# AdaptadorAcceso.net
KiCad netlist of a schematic drawn in EAGLE
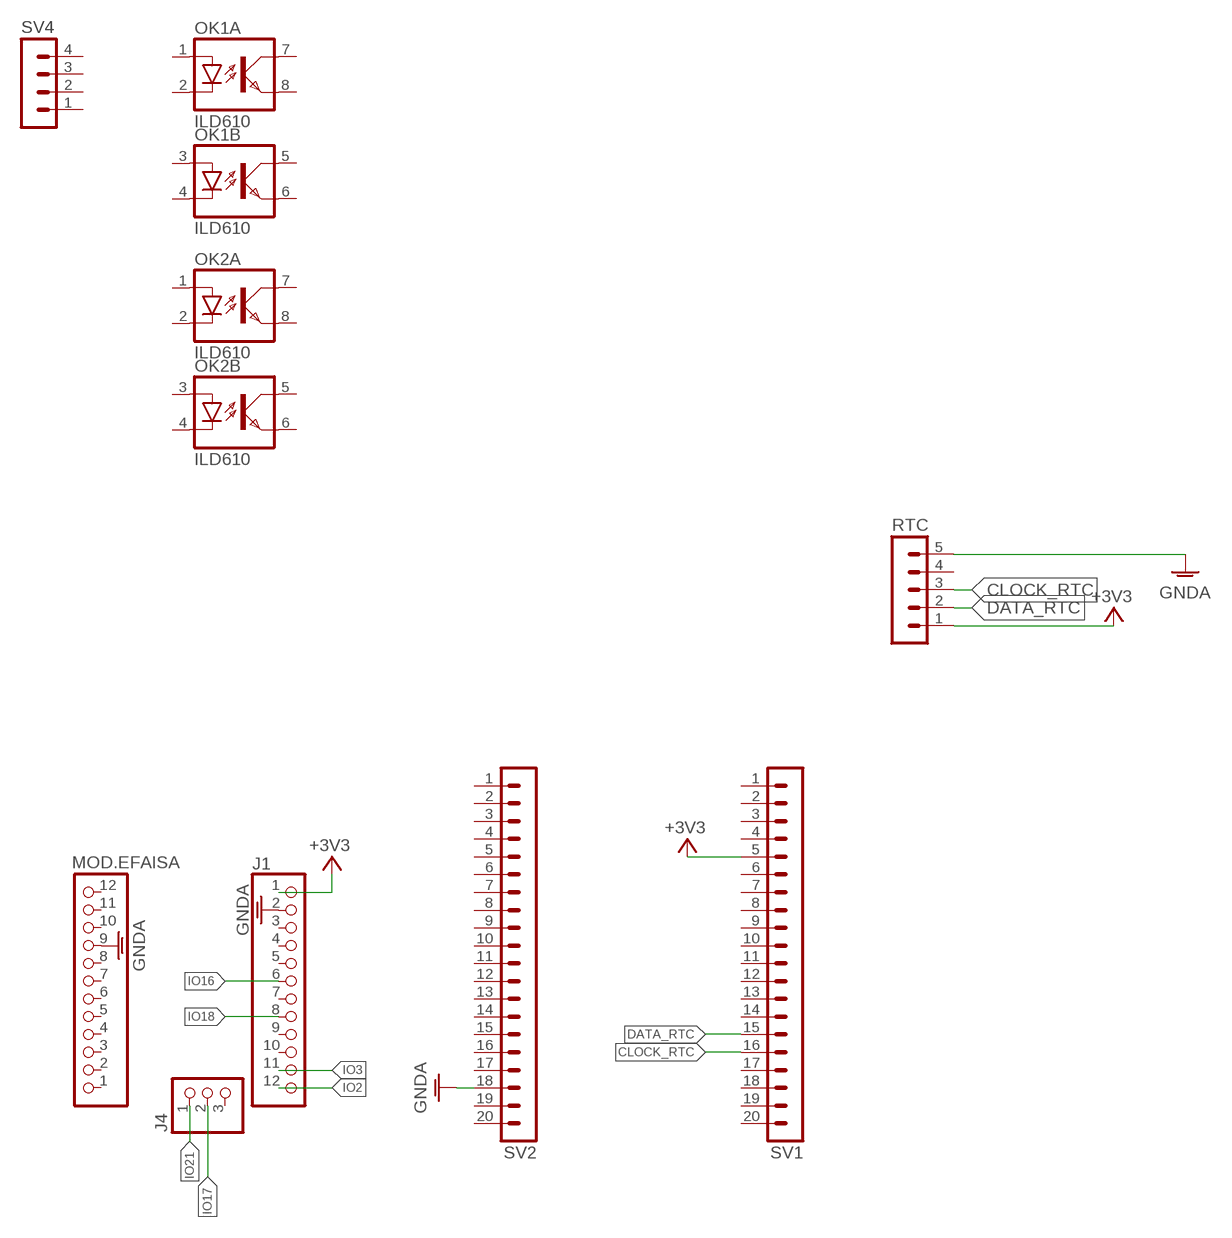
[diagram p0: schematic, sheet 1]

(export (version "E")
  (design (tool "Eeschema 10.0.6"))
  (components
    (comp (ref "J1")
      (value "PINHD-1X12")
      (footprint "eagle-import:1X12")
      (libsource (lib "eagle-import") (part "PINHD-1X12"))
    )
    (comp (ref "J4")
      (value "PINHD-1X3")
      (footprint "eagle-import:1X03")
      (libsource (lib "eagle-import") (part "PINHD-1X3"))
    )
    (comp (ref "MOD.EFAISA")
      (value "PINHD-1X12")
      (footprint "eagle-import:1X12")
      (libsource (lib "eagle-import") (part "PINHD-1X12"))
    )
    (comp (ref "OK1")
      (value "ILD610")
      (footprint "eagle-import:DIL08")
      (fields (field (name "MF") "VISHAY/TELEFUNKEN") (field (name "MPN") "ILD610-4"))
      (libsource (lib "eagle-import") (part "ILD610"))
    )
    (comp (ref "OK2")
      (value "ILD610")
      (footprint "eagle-import:DIL08")
      (fields (field (name "MF") "VISHAY/TELEFUNKEN") (field (name "MPN") "ILD610-4"))
      (libsource (lib "eagle-import") (part "ILD610"))
    )
    (comp (ref "RTC")
      (value "MA05-1")
      (footprint "eagle-import:MA05-1")
      (libsource (lib "eagle-import") (part "MA05-1"))
    )
    (comp (ref "SV1")
      (value "MA20-1L")
      (footprint "eagle-import:MA20-1L")
      (libsource (lib "eagle-import") (part "MA20-1L"))
    )
    (comp (ref "SV2")
      (value "MA20-1L")
      (footprint "eagle-import:MA20-1L")
      (libsource (lib "eagle-import") (part "MA20-1L"))
    )
    (comp (ref "SV4")
      (value "MA04-1")
      (footprint "eagle-import:MA04-1")
      (libsource (lib "eagle-import") (part "MA04-1"))
    )
  )
  (nets
    (net (code "1") (name "+3V3") (class "Default")
      (node (ref "J1") (pin "1") (pinfunction "1_1") (pintype "passive"))
      (node (ref "RTC") (pin "1") (pinfunction "1_1") (pintype "passive"))
      (node (ref "SV1") (pin "5") (pinfunction "5_5") (pintype "passive"))
    )
    (net (code "2") (name "CLOCK_RTC") (class "Default")
      (node (ref "RTC") (pin "3") (pinfunction "3_3") (pintype "passive"))
      (node (ref "SV1") (pin "16") (pinfunction "16_16") (pintype "passive"))
    )
    (net (code "3") (name "DATA_RTC") (class "Default")
      (node (ref "RTC") (pin "2") (pinfunction "2_2") (pintype "passive"))
      (node (ref "SV1") (pin "15") (pinfunction "15_15") (pintype "passive"))
    )
    (net (code "4") (name "GNDA") (class "Default")
      (node (ref "J1") (pin "2") (pinfunction "2_2") (pintype "passive"))
      (node (ref "MOD.EFAISA") (pin "9") (pinfunction "9_9") (pintype "passive"))
      (node (ref "RTC") (pin "5") (pinfunction "5_5") (pintype "passive"))
      (node (ref "SV2") (pin "18") (pinfunction "18_18") (pintype "passive"))
    )
    (net (code "5") (name "IO2") (class "Default")
      (node (ref "J1") (pin "12") (pinfunction "12_12") (pintype "passive"))
    )
    (net (code "6") (name "IO3") (class "Default")
      (node (ref "J1") (pin "11") (pinfunction "11_11") (pintype "passive"))
    )
    (net (code "7") (name "IO16") (class "Default")
      (node (ref "J1") (pin "6") (pinfunction "6_6") (pintype "passive"))
    )
    (net (code "8") (name "IO17") (class "Default")
      (node (ref "J4") (pin "2") (pinfunction "2_2") (pintype "passive"))
    )
    (net (code "9") (name "IO18") (class "Default")
      (node (ref "J1") (pin "8") (pinfunction "8_8") (pintype "passive"))
    )
    (net (code "10") (name "IO21") (class "Default")
      (node (ref "J4") (pin "1") (pinfunction "1_1") (pintype "passive"))
    )
    (net (code "11") (name "unconnected-(J1-Pad3)") (class "Default")
      (node (ref "J1") (pin "3") (pinfunction "3_3") (pintype "passive"))
    )
    (net (code "12") (name "unconnected-(J1-Pad4)") (class "Default")
      (node (ref "J1") (pin "4") (pinfunction "4_4") (pintype "passive"))
    )
    (net (code "13") (name "unconnected-(J1-Pad5)") (class "Default")
      (node (ref "J1") (pin "5") (pinfunction "5_5") (pintype "passive"))
    )
    (net (code "14") (name "unconnected-(J1-Pad7)") (class "Default")
      (node (ref "J1") (pin "7") (pinfunction "7_7") (pintype "passive"))
    )
    (net (code "15") (name "unconnected-(J1-Pad9)") (class "Default")
      (node (ref "J1") (pin "9") (pinfunction "9_9") (pintype "passive"))
    )
    (net (code "16") (name "unconnected-(J1-Pad10)") (class "Default")
      (node (ref "J1") (pin "10") (pinfunction "10_10") (pintype "passive"))
    )
    (net (code "17") (name "unconnected-(J4-Pad3)") (class "Default")
      (node (ref "J4") (pin "3") (pinfunction "3_3") (pintype "passive"))
    )
    (net (code "18") (name "unconnected-(MOD.EFAISA-Pad1)") (class "Default")
      (node (ref "MOD.EFAISA") (pin "1") (pinfunction "1_1") (pintype "passive"))
    )
    (net (code "19") (name "unconnected-(MOD.EFAISA-Pad2)") (class "Default")
      (node (ref "MOD.EFAISA") (pin "2") (pinfunction "2_2") (pintype "passive"))
    )
    (net (code "20") (name "unconnected-(MOD.EFAISA-Pad3)") (class "Default")
      (node (ref "MOD.EFAISA") (pin "3") (pinfunction "3_3") (pintype "passive"))
    )
    (net (code "21") (name "unconnected-(MOD.EFAISA-Pad4)") (class "Default")
      (node (ref "MOD.EFAISA") (pin "4") (pinfunction "4_4") (pintype "passive"))
    )
    (net (code "22") (name "unconnected-(MOD.EFAISA-Pad5)") (class "Default")
      (node (ref "MOD.EFAISA") (pin "5") (pinfunction "5_5") (pintype "passive"))
    )
    (net (code "23") (name "unconnected-(MOD.EFAISA-Pad6)") (class "Default")
      (node (ref "MOD.EFAISA") (pin "6") (pinfunction "6_6") (pintype "passive"))
    )
    (net (code "24") (name "unconnected-(MOD.EFAISA-Pad7)") (class "Default")
      (node (ref "MOD.EFAISA") (pin "7") (pinfunction "7_7") (pintype "passive"))
    )
    (net (code "25") (name "unconnected-(MOD.EFAISA-Pad8)") (class "Default")
      (node (ref "MOD.EFAISA") (pin "8") (pinfunction "8_8") (pintype "passive"))
    )
    (net (code "26") (name "unconnected-(MOD.EFAISA-Pad10)") (class "Default")
      (node (ref "MOD.EFAISA") (pin "10") (pinfunction "10_10") (pintype "passive"))
    )
    (net (code "27") (name "unconnected-(MOD.EFAISA-Pad11)") (class "Default")
      (node (ref "MOD.EFAISA") (pin "11") (pinfunction "11_11") (pintype "passive"))
    )
    (net (code "28") (name "unconnected-(MOD.EFAISA-Pad12)") (class "Default")
      (node (ref "MOD.EFAISA") (pin "12") (pinfunction "12_12") (pintype "passive"))
    )
    (net (code "29") (name "unconnected-(OK1A-A-Pad1)") (class "Default")
      (node (ref "OK1") (pin "1") (pinfunction "A_1") (pintype "passive"))
    )
    (net (code "30") (name "unconnected-(OK1A-C-Pad2)") (class "Default")
      (node (ref "OK1") (pin "2") (pinfunction "C_2") (pintype "passive"))
    )
    (net (code "31") (name "unconnected-(OK1A-COL-Pad7)") (class "Default")
      (node (ref "OK1") (pin "7") (pinfunction "COL_7") (pintype "passive"))
    )
    (net (code "32") (name "unconnected-(OK1A-EMIT-Pad8)") (class "Default")
      (node (ref "OK1") (pin "8") (pinfunction "EMIT_8") (pintype "passive"))
    )
    (net (code "33") (name "unconnected-(OK1B-A-Pad3)") (class "Default")
      (node (ref "OK1") (pin "3") (pinfunction "A_3") (pintype "passive"))
    )
    (net (code "34") (name "unconnected-(OK1B-C-Pad4)") (class "Default")
      (node (ref "OK1") (pin "4") (pinfunction "C_4") (pintype "passive"))
    )
    (net (code "35") (name "unconnected-(OK1B-COL-Pad5)") (class "Default")
      (node (ref "OK1") (pin "5") (pinfunction "COL_5") (pintype "passive"))
    )
    (net (code "36") (name "unconnected-(OK1B-EMIT-Pad6)") (class "Default")
      (node (ref "OK1") (pin "6") (pinfunction "EMIT_6") (pintype "passive"))
    )
    (net (code "37") (name "unconnected-(OK2A-A-Pad1)") (class "Default")
      (node (ref "OK2") (pin "1") (pinfunction "A_1") (pintype "passive"))
    )
    (net (code "38") (name "unconnected-(OK2A-C-Pad2)") (class "Default")
      (node (ref "OK2") (pin "2") (pinfunction "C_2") (pintype "passive"))
    )
    (net (code "39") (name "unconnected-(OK2A-COL-Pad7)") (class "Default")
      (node (ref "OK2") (pin "7") (pinfunction "COL_7") (pintype "passive"))
    )
    (net (code "40") (name "unconnected-(OK2A-EMIT-Pad8)") (class "Default")
      (node (ref "OK2") (pin "8") (pinfunction "EMIT_8") (pintype "passive"))
    )
    (net (code "41") (name "unconnected-(OK2B-A-Pad3)") (class "Default")
      (node (ref "OK2") (pin "3") (pinfunction "A_3") (pintype "passive"))
    )
    (net (code "42") (name "unconnected-(OK2B-C-Pad4)") (class "Default")
      (node (ref "OK2") (pin "4") (pinfunction "C_4") (pintype "passive"))
    )
    (net (code "43") (name "unconnected-(OK2B-COL-Pad5)") (class "Default")
      (node (ref "OK2") (pin "5") (pinfunction "COL_5") (pintype "passive"))
    )
    (net (code "44") (name "unconnected-(OK2B-EMIT-Pad6)") (class "Default")
      (node (ref "OK2") (pin "6") (pinfunction "EMIT_6") (pintype "passive"))
    )
    (net (code "45") (name "unconnected-(RTC-Pad4)") (class "Default")
      (node (ref "RTC") (pin "4") (pinfunction "4_4") (pintype "passive"))
    )
    (net (code "46") (name "unconnected-(SV1-Pad1)") (class "Default")
      (node (ref "SV1") (pin "1") (pinfunction "1_1") (pintype "passive"))
    )
    (net (code "47") (name "unconnected-(SV1-Pad2)") (class "Default")
      (node (ref "SV1") (pin "2") (pinfunction "2_2") (pintype "passive"))
    )
    (net (code "48") (name "unconnected-(SV1-Pad3)") (class "Default")
      (node (ref "SV1") (pin "3") (pinfunction "3_3") (pintype "passive"))
    )
    (net (code "49") (name "unconnected-(SV1-Pad4)") (class "Default")
      (node (ref "SV1") (pin "4") (pinfunction "4_4") (pintype "passive"))
    )
    (net (code "50") (name "unconnected-(SV1-Pad6)") (class "Default")
      (node (ref "SV1") (pin "6") (pinfunction "6_6") (pintype "passive"))
    )
    (net (code "51") (name "unconnected-(SV1-Pad7)") (class "Default")
      (node (ref "SV1") (pin "7") (pinfunction "7_7") (pintype "passive"))
    )
    (net (code "52") (name "unconnected-(SV1-Pad8)") (class "Default")
      (node (ref "SV1") (pin "8") (pinfunction "8_8") (pintype "passive"))
    )
    (net (code "53") (name "unconnected-(SV1-Pad9)") (class "Default")
      (node (ref "SV1") (pin "9") (pinfunction "9_9") (pintype "passive"))
    )
    (net (code "54") (name "unconnected-(SV1-Pad10)") (class "Default")
      (node (ref "SV1") (pin "10") (pinfunction "10_10") (pintype "passive"))
    )
    (net (code "55") (name "unconnected-(SV1-Pad11)") (class "Default")
      (node (ref "SV1") (pin "11") (pinfunction "11_11") (pintype "passive"))
    )
    (net (code "56") (name "unconnected-(SV1-Pad12)") (class "Default")
      (node (ref "SV1") (pin "12") (pinfunction "12_12") (pintype "passive"))
    )
    (net (code "57") (name "unconnected-(SV1-Pad13)") (class "Default")
      (node (ref "SV1") (pin "13") (pinfunction "13_13") (pintype "passive"))
    )
    (net (code "58") (name "unconnected-(SV1-Pad14)") (class "Default")
      (node (ref "SV1") (pin "14") (pinfunction "14_14") (pintype "passive"))
    )
    (net (code "59") (name "unconnected-(SV1-Pad17)") (class "Default")
      (node (ref "SV1") (pin "17") (pinfunction "17_17") (pintype "passive"))
    )
    (net (code "60") (name "unconnected-(SV1-Pad18)") (class "Default")
      (node (ref "SV1") (pin "18") (pinfunction "18_18") (pintype "passive"))
    )
    (net (code "61") (name "unconnected-(SV1-Pad19)") (class "Default")
      (node (ref "SV1") (pin "19") (pinfunction "19_19") (pintype "passive"))
    )
    (net (code "62") (name "unconnected-(SV1-Pad20)") (class "Default")
      (node (ref "SV1") (pin "20") (pinfunction "20_20") (pintype "passive"))
    )
    (net (code "63") (name "unconnected-(SV2-Pad1)") (class "Default")
      (node (ref "SV2") (pin "1") (pinfunction "1_1") (pintype "passive"))
    )
    (net (code "64") (name "unconnected-(SV2-Pad2)") (class "Default")
      (node (ref "SV2") (pin "2") (pinfunction "2_2") (pintype "passive"))
    )
    (net (code "65") (name "unconnected-(SV2-Pad3)") (class "Default")
      (node (ref "SV2") (pin "3") (pinfunction "3_3") (pintype "passive"))
    )
    (net (code "66") (name "unconnected-(SV2-Pad4)") (class "Default")
      (node (ref "SV2") (pin "4") (pinfunction "4_4") (pintype "passive"))
    )
    (net (code "67") (name "unconnected-(SV2-Pad5)") (class "Default")
      (node (ref "SV2") (pin "5") (pinfunction "5_5") (pintype "passive"))
    )
    (net (code "68") (name "unconnected-(SV2-Pad6)") (class "Default")
      (node (ref "SV2") (pin "6") (pinfunction "6_6") (pintype "passive"))
    )
    (net (code "69") (name "unconnected-(SV2-Pad7)") (class "Default")
      (node (ref "SV2") (pin "7") (pinfunction "7_7") (pintype "passive"))
    )
    (net (code "70") (name "unconnected-(SV2-Pad8)") (class "Default")
      (node (ref "SV2") (pin "8") (pinfunction "8_8") (pintype "passive"))
    )
    (net (code "71") (name "unconnected-(SV2-Pad9)") (class "Default")
      (node (ref "SV2") (pin "9") (pinfunction "9_9") (pintype "passive"))
    )
    (net (code "72") (name "unconnected-(SV2-Pad10)") (class "Default")
      (node (ref "SV2") (pin "10") (pinfunction "10_10") (pintype "passive"))
    )
    (net (code "73") (name "unconnected-(SV2-Pad11)") (class "Default")
      (node (ref "SV2") (pin "11") (pinfunction "11_11") (pintype "passive"))
    )
    (net (code "74") (name "unconnected-(SV2-Pad12)") (class "Default")
      (node (ref "SV2") (pin "12") (pinfunction "12_12") (pintype "passive"))
    )
    (net (code "75") (name "unconnected-(SV2-Pad13)") (class "Default")
      (node (ref "SV2") (pin "13") (pinfunction "13_13") (pintype "passive"))
    )
    (net (code "76") (name "unconnected-(SV2-Pad14)") (class "Default")
      (node (ref "SV2") (pin "14") (pinfunction "14_14") (pintype "passive"))
    )
    (net (code "77") (name "unconnected-(SV2-Pad15)") (class "Default")
      (node (ref "SV2") (pin "15") (pinfunction "15_15") (pintype "passive"))
    )
    (net (code "78") (name "unconnected-(SV2-Pad16)") (class "Default")
      (node (ref "SV2") (pin "16") (pinfunction "16_16") (pintype "passive"))
    )
    (net (code "79") (name "unconnected-(SV2-Pad17)") (class "Default")
      (node (ref "SV2") (pin "17") (pinfunction "17_17") (pintype "passive"))
    )
    (net (code "80") (name "unconnected-(SV2-Pad19)") (class "Default")
      (node (ref "SV2") (pin "19") (pinfunction "19_19") (pintype "passive"))
    )
    (net (code "81") (name "unconnected-(SV2-Pad20)") (class "Default")
      (node (ref "SV2") (pin "20") (pinfunction "20_20") (pintype "passive"))
    )
    (net (code "82") (name "unconnected-(SV4-Pad1)") (class "Default")
      (node (ref "SV4") (pin "1") (pinfunction "1_1") (pintype "passive"))
    )
    (net (code "83") (name "unconnected-(SV4-Pad2)") (class "Default")
      (node (ref "SV4") (pin "2") (pinfunction "2_2") (pintype "passive"))
    )
    (net (code "84") (name "unconnected-(SV4-Pad3)") (class "Default")
      (node (ref "SV4") (pin "3") (pinfunction "3_3") (pintype "passive"))
    )
    (net (code "85") (name "unconnected-(SV4-Pad4)") (class "Default")
      (node (ref "SV4") (pin "4") (pinfunction "4_4") (pintype "passive"))
    )
  )
)
